# Keng_Seng_-_3rd_Step_Down_Circuit.net
KiCad netlist of a schematic drawn in Altium Designer
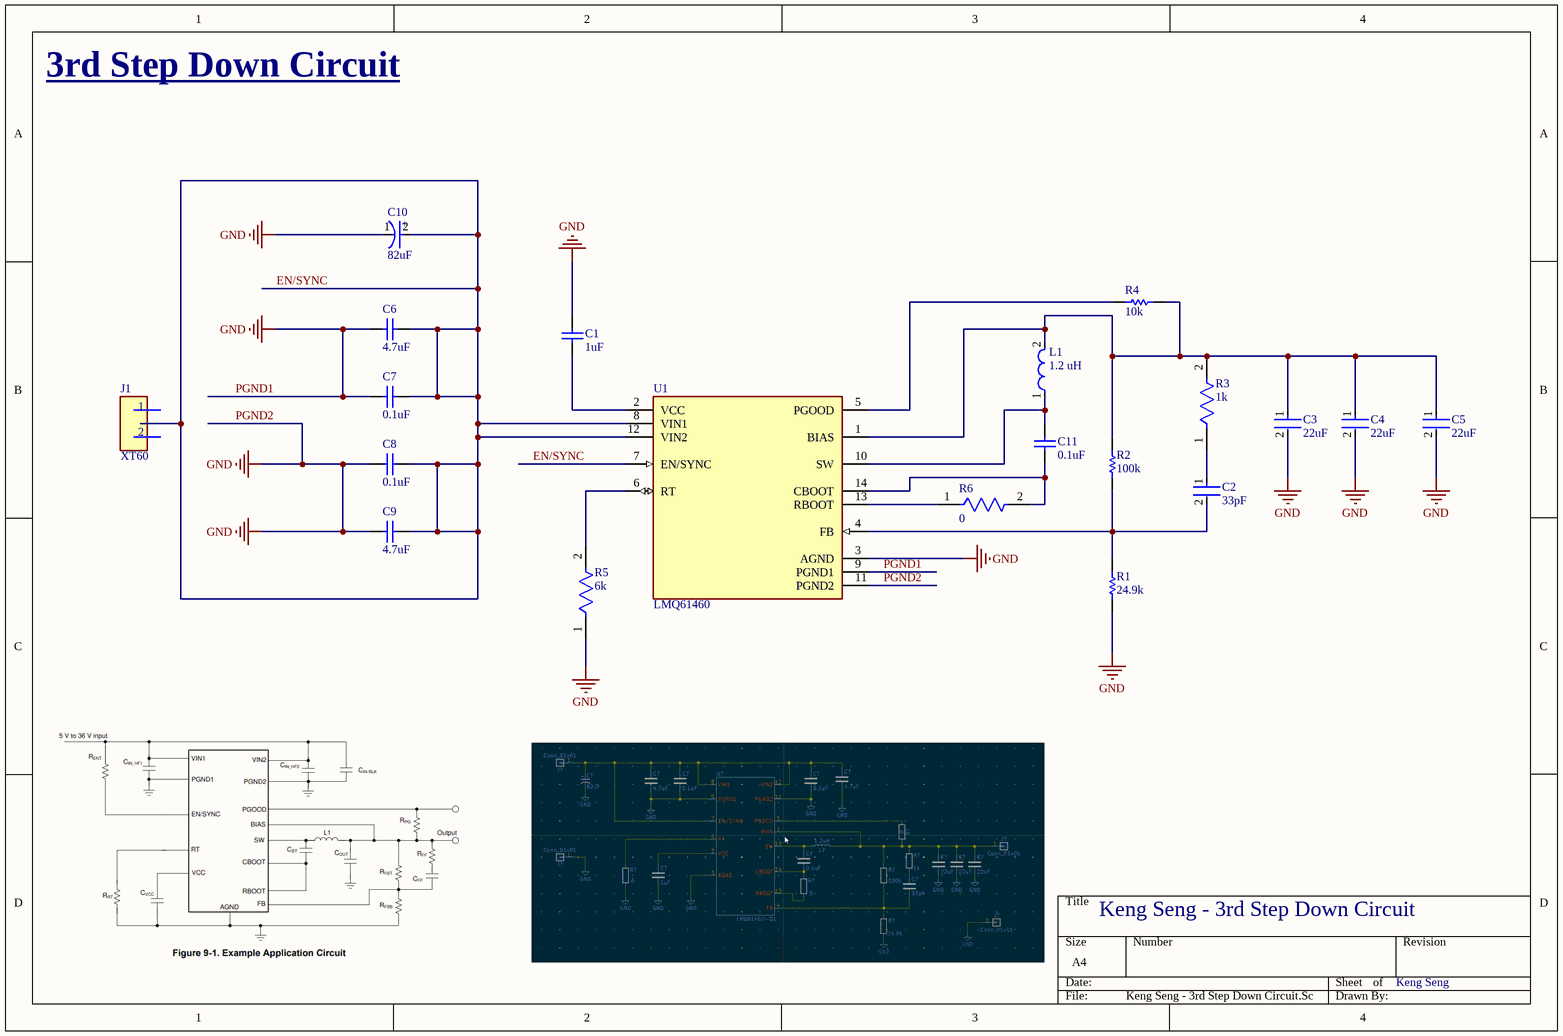
[diagram p0: Keng Seng - 3rd Step Down Circuit.SchDoc]

(export (version "E")
  (design (tool "Eeschema 10.0.6"))
  (components
    (comp (ref "C1")
      (value "1uF")
      (footprint "CAPC2013X135X45LL10T25")
      (fields (field (name "MANUFACTURER") "Murata") (field (name "PART NUMBER") "GRM21BR71H105KA12L"))
      (libsource (lib "Altium Content Vault") (part "CAP"))
    )
    (comp (ref "C2")
      (value "33pF")
      (footprint "FP-CC0603-0_9-IPC_C")
      (description "CAP CER 33PF 50V C0G/NPO 0603")
      (fields (field (name "TOLERANCE") "5%") (field (name "VOLTAGE") "50V"))
      (libsource (lib "Altium Content Vault") (part "b4654b650e69147ec39a6b967a45e02"))
    )
    (comp (ref "C3")
      (value "22uF")
      (footprint "FP-GRM21B-0_15-MFG")
      (description "Chip Multilayer Ceramic Capacitors for General Purpose, 0805, 22uF, X5R, 15%, 20%, 6.3V")
      (fields (field (name "VOLTAGE") "6.3V") (field (name "TOLERANCE") "20%"))
      (libsource (lib "Altium Content Vault") (part "b4654b650e69147ec39a6b967a45e02"))
    )
    (comp (ref "C4")
      (value "22uF")
      (footprint "FP-GRM21B-0_15-MFG")
      (description "Chip Multilayer Ceramic Capacitors for General Purpose, 0805, 22uF, X5R, 15%, 20%, 6.3V")
      (fields (field (name "VOLTAGE") "6.3V") (field (name "TOLERANCE") "20%"))
      (libsource (lib "Altium Content Vault") (part "b4654b650e69147ec39a6b967a45e02"))
    )
    (comp (ref "C5")
      (value "22uF")
      (footprint "FP-GRM21B-0_15-MFG")
      (description "Chip Multilayer Ceramic Capacitors for General Purpose, 0805, 22uF, X5R, 15%, 20%, 6.3V")
      (fields (field (name "VOLTAGE") "6.3V") (field (name "TOLERANCE") "20%"))
      (libsource (lib "Altium Content Vault") (part "b4654b650e69147ec39a6b967a45e02"))
    )
    (comp (ref "C6")
      (value "4.7uF")
      (footprint "CAPC2013X135X45LL10T25")
      (description "Chip Capacitor, 4.7 uF, +/- 10%, 16 V, -55 to 85 degC, 0805 (2012 Metric), RoHS, Tape and Reel")
      (fields (field (name "TOLERANCE") "10%") (field (name "PARTNUMBER") "GRM21BR61C475KA88L"))
      (libsource (lib "Altium Content Vault") (part "CAP-NP-2"))
    )
    (comp (ref "C7")
      (value "0.1uF")
      (footprint "CAPC1005X55X30LL05T10")
      (fields (field (name "MANUFACTURER") "Kemet") (field (name "PART NUMBER") "C0402C104K4RACTU"))
      (libsource (lib "Altium Content Vault") (part "CAP"))
    )
    (comp (ref "C8")
      (value "0.1uF")
      (footprint "CAPC1005X55X30LL05T10")
      (fields (field (name "MANUFACTURER") "Kemet") (field (name "PART NUMBER") "C0402C104K4RACTU"))
      (libsource (lib "Altium Content Vault") (part "CAP"))
    )
    (comp (ref "C9")
      (value "4.7uF")
      (footprint "CAPC2013X135X45LL10T25")
      (description "Chip Capacitor, 4.7 uF, +/- 10%, 16 V, -55 to 85 degC, 0805 (2012 Metric), RoHS, Tape and Reel")
      (fields (field (name "TOLERANCE") "10%") (field (name "PARTNUMBER") "GRM21BR61C475KA88L"))
      (libsource (lib "Altium Content Vault") (part "CAP-NP-2"))
    )
    (comp (ref "C10")
      (value "82uF")
      (footprint "FP-OS-CON-SMT-E12-MFG")
      (description "Conductive Polymer Aluminum Solid Capacitors (OS-CON) 82uF ±20% 35V")
      (fields (field (name "TOLERANCE") "20%") (field (name "VOLTAGE") "35V"))
      (libsource (lib "Altium Content Vault") (part "a00bbbee19879c290e62620ae7e47b1"))
    )
    (comp (ref "C11")
      (value "0.1uF")
      (footprint "CAPC1005X55X30LL05T10")
      (fields (field (name "MANUFACTURER") "Kemet") (field (name "PART NUMBER") "C0402C104K4RACTU"))
      (libsource (lib "Altium Content Vault") (part "CAP"))
    )
    (comp (ref "J1")
      (value "XT60")
      (footprint "FP-PRT-10474-MFG")
      (description "XT60 CONNECTORS MALE/FEMALE PAIR")
      (libsource (lib "Altium Content Vault") (part "e9d95e9eb6564353a08a501d7ea6c79"))
    )
    (comp (ref "L1")
      (value "1.2 uH")
      (footprint "FP-IHLP-5050FD-FP_2_945x4-MFG")
      (description "Commercial Inductors, High Saturation Series 1.2uH 30A 2.5mΩ 20%")
      (fields (field (name "TOLERANCE") "20%"))
      (libsource (lib "Altium Content Vault") (part "725321dda6339637d4d059423bc1c3c"))
    )
    (comp (ref "R1")
      (value "24.9k")
      (footprint "RESC1609X55X30ML10T20")
      (fields (field (name "PART NUMBER") "TNPW060324R9BEEA") (field (name "MANUFACTURER") "Vishay Dale"))
      (libsource (lib "Altium Content Vault") (part "RES"))
    )
    (comp (ref "R2")
      (value "100k")
      (footprint "RESC0603X26X15LL03T05")
      (fields (field (name "PART NUMBER") "MCCN-41JL6--100K") (field (name "MANUFACTURER") "Multicomp"))
      (libsource (lib "Altium Content Vault") (part "RES"))
    )
    (comp (ref "R3")
      (value "1k")
      (footprint "FP-RC0402-0_4-IPC_A")
      (description "RES 1K OHM 1% 1/16W 0402")
      (fields (field (name "TOLERANCE") "1%"))
      (libsource (lib "Altium Content Vault") (part "1029c3af85768c4190bb7ad29bc67b5"))
    )
    (comp (ref "R4")
      (value "10k")
      (footprint "RESC1609X50X30NL8T20")
      (description "Chip Resistor, 10 KOhm, +/- 1%, 100 mW, -55 to 155 degC, 0603 (1608 Metric), RoHS, Tape and Reel")
      (fields (field (name "MANUFACTURER") "Vishay Semiconductor"))
      (libsource (lib "Altium Content Vault") (part "RES-2"))
    )
    (comp (ref "R5")
      (value "6k")
      (footprint "FP-RN732B-IPC_C")
      (description "6kΩ ±0.1% 0.125W, 1/8W Chip Resistor 1206 (3216 Metric) Moisture Resistant Thin Film")
      (fields (field (name "TOLERANCE") "0.1%"))
      (libsource (lib "Altium Content Vault") (part "1029c3af85768c4190bb7ad29bc67b5"))
    )
    (comp (ref "R6")
      (value "0")
      (footprint "FP-CRCW0402-e3-IPC_C")
      (description "RES Thick Film, 0Ω, 0.063W, 0402")
      (fields (field (name "TOLERANCE") "5%"))
      (libsource (lib "Altium Content Vault") (part "1029c3af85768c4190bb7ad29bc67b5"))
    )
    (comp (ref "U1")
      (value "LMQ61460")
      (footprint "FP-RJR0014A-MFG")
      (description "AUTOMOTIVE 3-V TO 36-V, 6-A LOW")
      (libsource (lib "Altium Content Vault") (part "582341cdab2d02ffbfc5ca31c7a38c5"))
    )
  )
  (nets
    (net (code "1") (name "/EN{slash}SYNC") (class "Default")
      (node (ref "C10") (pin "2") (pinfunction "A_2") (pintype "passive"))
      (node (ref "C6") (pin "2") (pinfunction "2_2") (pintype "passive"))
      (node (ref "C7") (pin "2") (pinfunction "2_2") (pintype "passive"))
      (node (ref "C8") (pin "2") (pinfunction "2_2") (pintype "passive"))
      (node (ref "C9") (pin "2") (pinfunction "2_2") (pintype "passive"))
      (node (ref "U1") (pin "12") (pinfunction "VIN2_12") (pintype "power_in"))
      (node (ref "U1") (pin "7") (pinfunction "EN/SYNC_7") (pintype "input"))
      (node (ref "U1") (pin "8") (pinfunction "VIN1_8") (pintype "power_in"))
    )
    (net (code "2") (name "GND") (class "Default")
      (node (ref "C1") (pin "2") (pinfunction "2_2") (pintype "passive"))
      (node (ref "C10") (pin "1") (pinfunction "C_1") (pintype "passive"))
      (node (ref "C3") (pin "2") (pinfunction "2_2") (pintype "passive"))
      (node (ref "C4") (pin "2") (pinfunction "2_2") (pintype "passive"))
      (node (ref "C5") (pin "2") (pinfunction "2_2") (pintype "passive"))
      (node (ref "C6") (pin "1") (pinfunction "1_1") (pintype "passive"))
      (node (ref "C7") (pin "1") (pinfunction "1_1") (pintype "passive"))
      (node (ref "C8") (pin "1") (pinfunction "1_1") (pintype "passive"))
      (node (ref "C9") (pin "1") (pinfunction "1_1") (pintype "passive"))
      (node (ref "R1") (pin "1") (pinfunction "1_1") (pintype "passive"))
      (node (ref "R5") (pin "1") (pinfunction "1_1") (pintype "passive"))
      (node (ref "U1") (pin "11") (pinfunction "PGND2_11") (pintype "power_in"))
      (node (ref "U1") (pin "3") (pinfunction "AGND_3") (pintype "power_in"))
      (node (ref "U1") (pin "9") (pinfunction "PGND1_9") (pintype "power_in"))
    )
    (net (code "3") (name "Net-(C2-Pad1)") (class "Default")
      (node (ref "C2") (pin "1") (pinfunction "1_1") (pintype "passive"))
      (node (ref "R3") (pin "1") (pinfunction "1_1") (pintype "passive"))
    )
    (net (code "4") (name "Net-(U1-BIAS)") (class "Default")
      (node (ref "C3") (pin "1") (pinfunction "1_1") (pintype "passive"))
      (node (ref "C4") (pin "1") (pinfunction "1_1") (pintype "passive"))
      (node (ref "C5") (pin "1") (pinfunction "1_1") (pintype "passive"))
      (node (ref "L1") (pin "2") (pinfunction "2_2") (pintype "passive"))
      (node (ref "R2") (pin "2") (pinfunction "2_2") (pintype "passive"))
      (node (ref "R3") (pin "2") (pinfunction "2_2") (pintype "passive"))
      (node (ref "R4") (pin "2") (pinfunction "2_2") (pintype "passive"))
      (node (ref "U1") (pin "1") (pinfunction "BIAS_1") (pintype "passive"))
    )
    (net (code "5") (name "Net-(U1-CBOOT)") (class "Default")
      (node (ref "C11") (pin "1") (pinfunction "1_1") (pintype "passive"))
      (node (ref "R6") (pin "2") (pinfunction "2_2") (pintype "passive"))
      (node (ref "U1") (pin "14") (pinfunction "CBOOT_14") (pintype "passive"))
    )
    (net (code "6") (name "Net-(U1-FB)") (class "Default")
      (node (ref "C2") (pin "2") (pinfunction "2_2") (pintype "passive"))
      (node (ref "R1") (pin "2") (pinfunction "2_2") (pintype "passive"))
      (node (ref "R2") (pin "1") (pinfunction "1_1") (pintype "passive"))
      (node (ref "U1") (pin "4") (pinfunction "FB_4") (pintype "input"))
    )
    (net (code "7") (name "Net-(U1-PGOOD)") (class "Default")
      (node (ref "R4") (pin "1") (pinfunction "1_1") (pintype "passive"))
      (node (ref "U1") (pin "5") (pinfunction "PGOOD_5") (pintype "open_collector"))
    )
    (net (code "8") (name "Net-(U1-RBOOT)") (class "Default")
      (node (ref "R6") (pin "1") (pinfunction "1_1") (pintype "passive"))
      (node (ref "U1") (pin "13") (pinfunction "RBOOT_13") (pintype "passive"))
    )
    (net (code "9") (name "Net-(U1-RT)") (class "Default")
      (node (ref "R5") (pin "2") (pinfunction "2_2") (pintype "passive"))
      (node (ref "U1") (pin "6") (pinfunction "RT_6") (pintype "bidirectional"))
    )
    (net (code "10") (name "Net-(U1-SW)") (class "Default")
      (node (ref "C11") (pin "2") (pinfunction "2_2") (pintype "passive"))
      (node (ref "L1") (pin "1") (pinfunction "1_1") (pintype "passive"))
      (node (ref "U1") (pin "10") (pinfunction "SW_10") (pintype "passive"))
    )
    (net (code "11") (name "Net-(U1-VCC)") (class "Default")
      (node (ref "C1") (pin "1") (pinfunction "1_1") (pintype "passive"))
      (node (ref "U1") (pin "2") (pinfunction "VCC_2") (pintype "power_in"))
    )
  )
)
